# 06_SHL.net
KiCad netlist of a schematic drawn in EAGLE
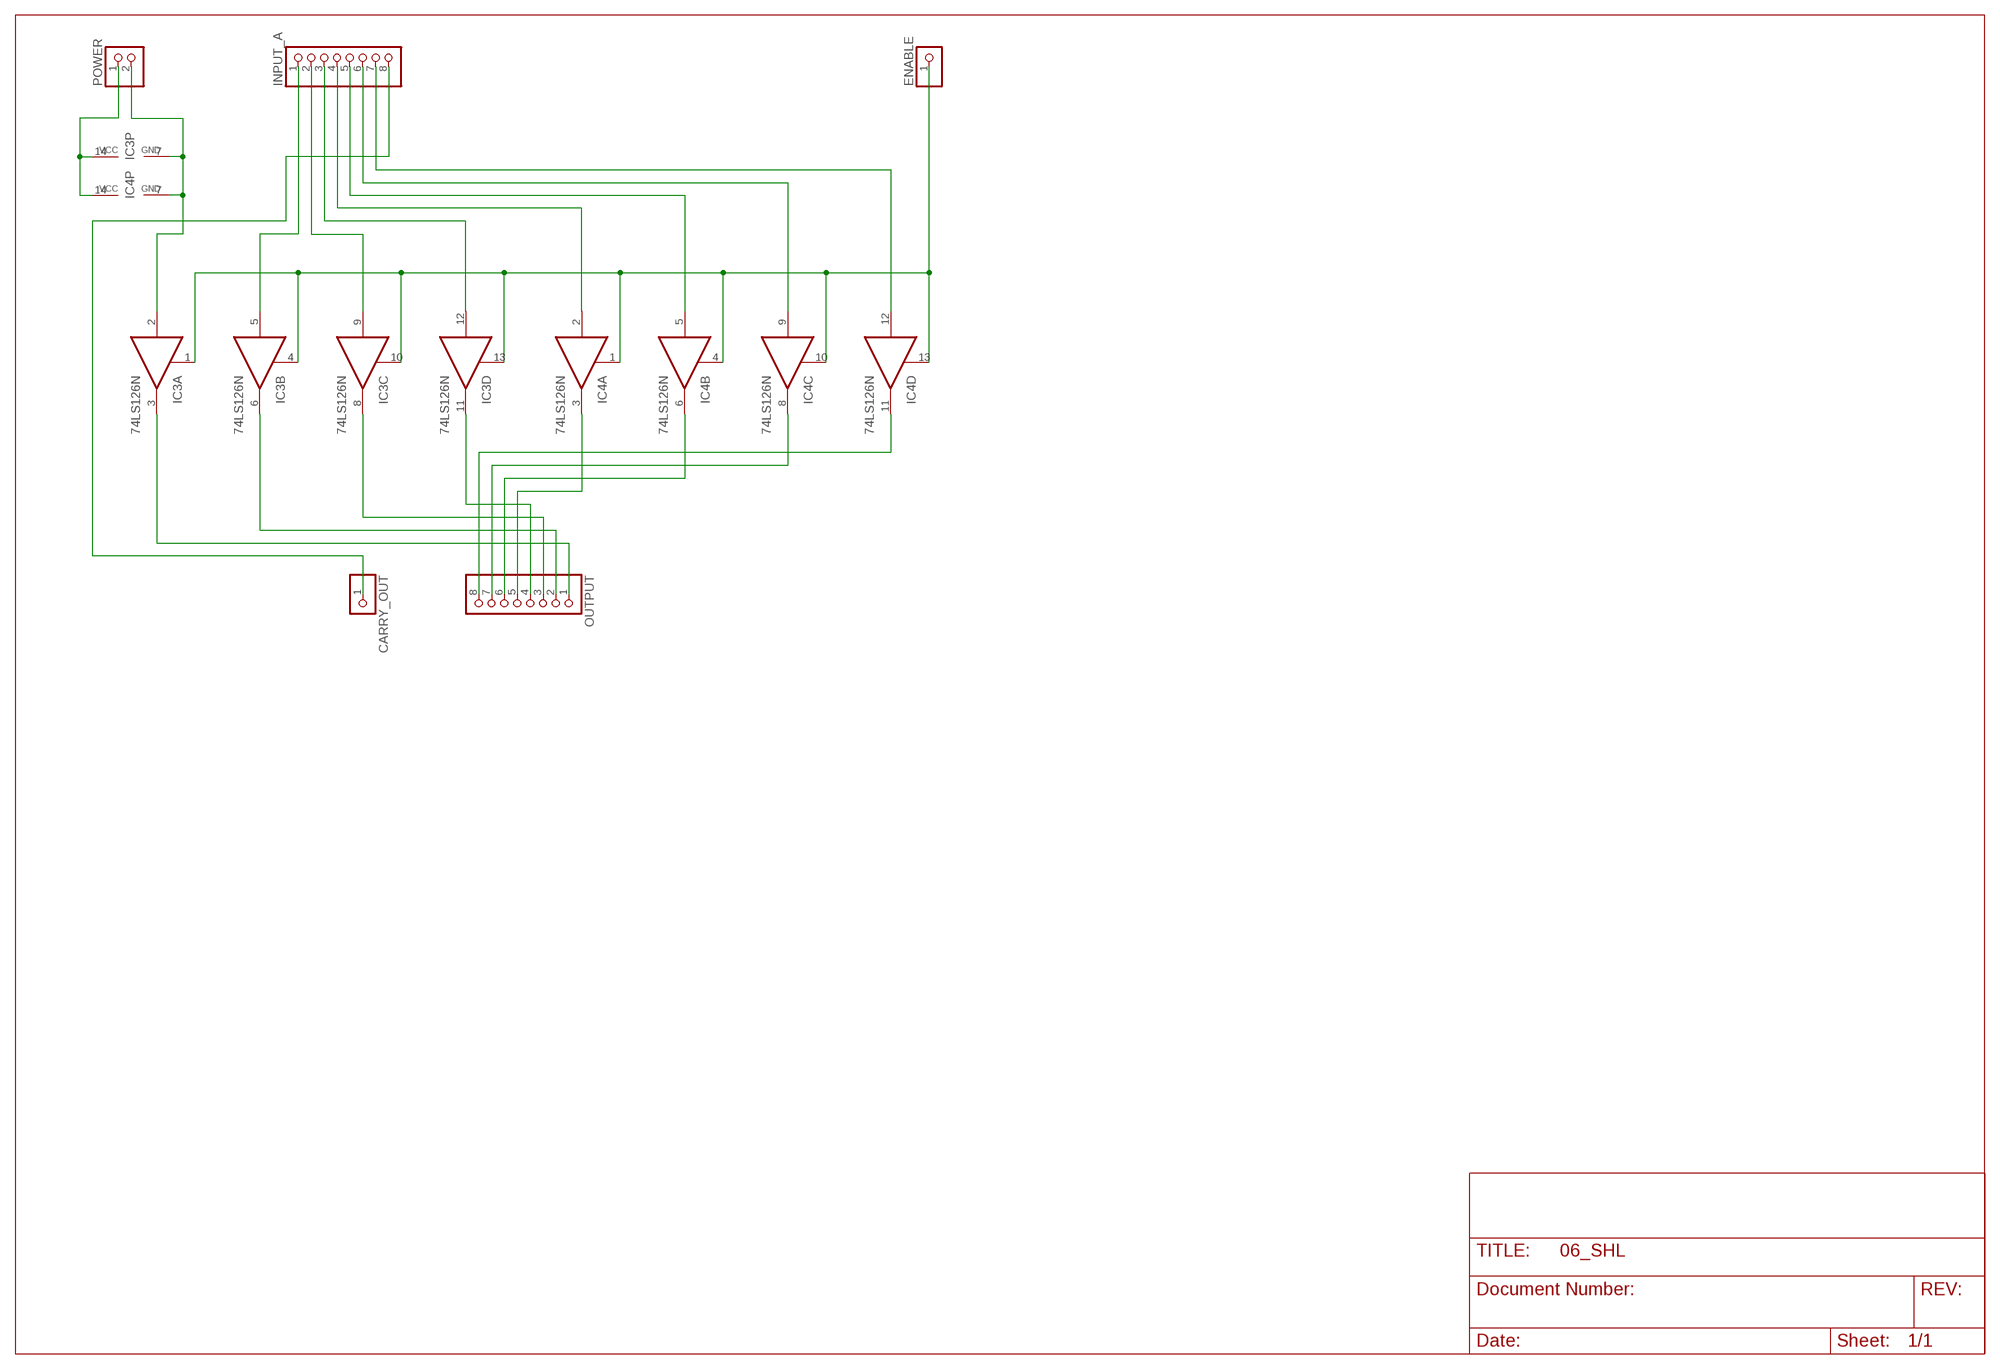
[diagram p0: schematic, sheet 1]

(export (version "E")
  (design (tool "Eeschema 10.0.6"))
  (components
    (comp (ref "CARRY_OUT")
      (value "PINHD-1X1")
      (footprint "eagle-import:1X01")
      (libsource (lib "eagle-import") (part "PINHD-1X1"))
    )
    (comp (ref "ENABLE")
      (value "PINHD-1X1")
      (footprint "eagle-import:1X01")
      (libsource (lib "eagle-import") (part "PINHD-1X1"))
    )
    (comp (ref "IC3")
      (value "74LS126N")
      (footprint "eagle-import:DIL14")
      (libsource (lib "eagle-import") (part "74126NLS"))
    )
    (comp (ref "IC4")
      (value "74LS126N")
      (footprint "eagle-import:DIL14")
      (libsource (lib "eagle-import") (part "74126NLS"))
    )
    (comp (ref "INPUT_A")
      (value "PINHD-1X8")
      (footprint "eagle-import:1X08")
      (libsource (lib "eagle-import") (part "PINHD-1X8"))
    )
    (comp (ref "OUTPUT")
      (value "PINHD-1X8")
      (footprint "eagle-import:1X08")
      (libsource (lib "eagle-import") (part "PINHD-1X8"))
    )
    (comp (ref "POWER")
      (value "PINHD-1X2")
      (footprint "eagle-import:1X02")
      (libsource (lib "eagle-import") (part "PINHD-1X2"))
    )
  )
  (nets
    (net (code "1") (name "Net-(CARRY_OUT-Pad1)") (class "Default")
      (node (ref "CARRY_OUT") (pin "1") (pinfunction "1_1") (pintype "passive"))
      (node (ref "INPUT_A") (pin "8") (pinfunction "8_8") (pintype "passive"))
    )
    (net (code "2") (name "Net-(IC3A-I)") (class "Default")
      (node (ref "IC3") (pin "2") (pinfunction "I_2") (pintype "input"))
      (node (ref "IC3") (pin "7") (pinfunction "GND_7") (pintype "power_in"))
      (node (ref "IC4") (pin "7") (pinfunction "GND_7") (pintype "power_in"))
      (node (ref "POWER") (pin "2") (pinfunction "2_2") (pintype "passive"))
    )
    (net (code "3") (name "Net-(IC3A-O)") (class "Default")
      (node (ref "IC3") (pin "3") (pinfunction "O_3") (pintype "output"))
      (node (ref "OUTPUT") (pin "1") (pinfunction "1_1") (pintype "passive"))
    )
    (net (code "4") (name "Net-(IC3A-OE)") (class "Default")
      (node (ref "ENABLE") (pin "1") (pinfunction "1_1") (pintype "passive"))
      (node (ref "IC3") (pin "1") (pinfunction "OE_1") (pintype "input"))
      (node (ref "IC3") (pin "10") (pinfunction "OE_10") (pintype "input"))
      (node (ref "IC3") (pin "13") (pinfunction "OE_13") (pintype "input"))
      (node (ref "IC3") (pin "4") (pinfunction "OE_4") (pintype "input"))
      (node (ref "IC4") (pin "1") (pinfunction "OE_1") (pintype "input"))
      (node (ref "IC4") (pin "10") (pinfunction "OE_10") (pintype "input"))
      (node (ref "IC4") (pin "13") (pinfunction "OE_13") (pintype "input"))
      (node (ref "IC4") (pin "4") (pinfunction "OE_4") (pintype "input"))
    )
    (net (code "5") (name "Net-(IC3B-I)") (class "Default")
      (node (ref "IC3") (pin "5") (pinfunction "I_5") (pintype "input"))
      (node (ref "INPUT_A") (pin "1") (pinfunction "1_1") (pintype "passive"))
    )
    (net (code "6") (name "Net-(IC3B-O)") (class "Default")
      (node (ref "IC3") (pin "6") (pinfunction "O_6") (pintype "output"))
      (node (ref "OUTPUT") (pin "2") (pinfunction "2_2") (pintype "passive"))
    )
    (net (code "7") (name "Net-(IC3C-I)") (class "Default")
      (node (ref "IC3") (pin "9") (pinfunction "I_9") (pintype "input"))
      (node (ref "INPUT_A") (pin "2") (pinfunction "2_2") (pintype "passive"))
    )
    (net (code "8") (name "Net-(IC3C-O)") (class "Default")
      (node (ref "IC3") (pin "8") (pinfunction "O_8") (pintype "output"))
      (node (ref "OUTPUT") (pin "3") (pinfunction "3_3") (pintype "passive"))
    )
    (net (code "9") (name "Net-(IC3D-I)") (class "Default")
      (node (ref "IC3") (pin "12") (pinfunction "I_12") (pintype "input"))
      (node (ref "INPUT_A") (pin "3") (pinfunction "3_3") (pintype "passive"))
    )
    (net (code "10") (name "Net-(IC3D-O)") (class "Default")
      (node (ref "IC3") (pin "11") (pinfunction "O_11") (pintype "output"))
      (node (ref "OUTPUT") (pin "4") (pinfunction "4_4") (pintype "passive"))
    )
    (net (code "11") (name "Net-(IC3E-VCC)") (class "Default")
      (node (ref "IC3") (pin "14") (pinfunction "VCC_14") (pintype "power_in"))
      (node (ref "IC4") (pin "14") (pinfunction "VCC_14") (pintype "power_in"))
      (node (ref "POWER") (pin "1") (pinfunction "1_1") (pintype "passive"))
    )
    (net (code "12") (name "Net-(IC4A-I)") (class "Default")
      (node (ref "IC4") (pin "2") (pinfunction "I_2") (pintype "input"))
      (node (ref "INPUT_A") (pin "4") (pinfunction "4_4") (pintype "passive"))
    )
    (net (code "13") (name "Net-(IC4A-O)") (class "Default")
      (node (ref "IC4") (pin "3") (pinfunction "O_3") (pintype "output"))
      (node (ref "OUTPUT") (pin "5") (pinfunction "5_5") (pintype "passive"))
    )
    (net (code "14") (name "Net-(IC4B-I)") (class "Default")
      (node (ref "IC4") (pin "5") (pinfunction "I_5") (pintype "input"))
      (node (ref "INPUT_A") (pin "5") (pinfunction "5_5") (pintype "passive"))
    )
    (net (code "15") (name "Net-(IC4B-O)") (class "Default")
      (node (ref "IC4") (pin "6") (pinfunction "O_6") (pintype "output"))
      (node (ref "OUTPUT") (pin "6") (pinfunction "6_6") (pintype "passive"))
    )
    (net (code "16") (name "Net-(IC4C-I)") (class "Default")
      (node (ref "IC4") (pin "9") (pinfunction "I_9") (pintype "input"))
      (node (ref "INPUT_A") (pin "6") (pinfunction "6_6") (pintype "passive"))
    )
    (net (code "17") (name "Net-(IC4C-O)") (class "Default")
      (node (ref "IC4") (pin "8") (pinfunction "O_8") (pintype "output"))
      (node (ref "OUTPUT") (pin "7") (pinfunction "7_7") (pintype "passive"))
    )
    (net (code "18") (name "Net-(IC4D-I)") (class "Default")
      (node (ref "IC4") (pin "12") (pinfunction "I_12") (pintype "input"))
      (node (ref "INPUT_A") (pin "7") (pinfunction "7_7") (pintype "passive"))
    )
    (net (code "19") (name "Net-(IC4D-O)") (class "Default")
      (node (ref "IC4") (pin "11") (pinfunction "O_11") (pintype "output"))
      (node (ref "OUTPUT") (pin "8") (pinfunction "8_8") (pintype "passive"))
    )
  )
)
